# MCP73831_Li-Ion_charge.net
KiCad netlist of a schematic drawn in Altium Designer
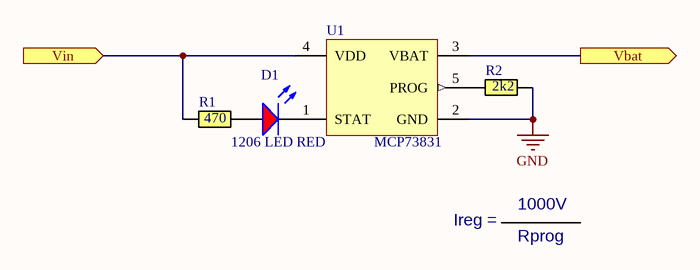
[diagram p0: MCP73831 Li-Ion charge.SchDoc]

(export (version "E")
  (design (tool "Eeschema 10.0.6"))
  (components
    (comp (ref "D1")
      (value "1206 LED RED")
      (footprint "1206 LED RED")
      (libsource (lib "LEDs_Optical") (part "1206 LED RED"))
    )
    (comp (ref "R1")
      (value "470")
      (footprint "RESC0603(1608)_N")
      (description "Resistor Medium Density")
      (libsource (lib "Discrete_Passive_RCL") (part "Resistor M"))
    )
    (comp (ref "R2")
      (value "2k2")
      (footprint "RESC0603(1608)_N")
      (description "Resistor Medium Density")
      (libsource (lib "Discrete_Passive_RCL") (part "Resistor M"))
    )
    (comp (ref "U1")
      (value "MCP73831")
      (footprint "SOT23-5")
      (description "Linear Charge Management Controller")
      (libsource (lib "IntegrationCircuits") (part "MCP73831"))
    )
  )
  (nets
    (net (code "1") (name "/Vbat") (class "Default")
      (node (ref "U1") (pin "3") (pinfunction "VBAT_3") (pintype "power_in"))
    )
    (net (code "2") (name "/Vin") (class "Default")
      (node (ref "R1") (pin "1") (pinfunction "1_1") (pintype "passive"))
      (node (ref "U1") (pin "4") (pinfunction "VDD_4") (pintype "power_in"))
    )
    (net (code "3") (name "GND") (class "Default")
      (node (ref "R2") (pin "2") (pinfunction "2_2") (pintype "passive"))
      (node (ref "U1") (pin "2") (pinfunction "GND_2") (pintype "power_in"))
    )
    (net (code "4") (name "Net-(D1-PadA)") (class "Default")
      (node (ref "D1") (pin "A") (pinfunction "A_A") (pintype "passive"))
      (node (ref "R1") (pin "2") (pinfunction "2_2") (pintype "passive"))
    )
    (net (code "5") (name "Net-(U1-PROG)") (class "Default")
      (node (ref "R2") (pin "1") (pinfunction "1_1") (pintype "passive"))
      (node (ref "U1") (pin "5") (pinfunction "PROG_5") (pintype "output"))
    )
    (net (code "6") (name "Net-(U1-STAT)") (class "Default")
      (node (ref "D1") (pin "K") (pinfunction "K_K") (pintype "passive"))
      (node (ref "U1") (pin "1") (pinfunction "STAT_1") (pintype "open_collector"))
    )
  )
)
